# APD9328_FPGA_BANK.net
KiCad netlist of a schematic drawn in Altium Designer
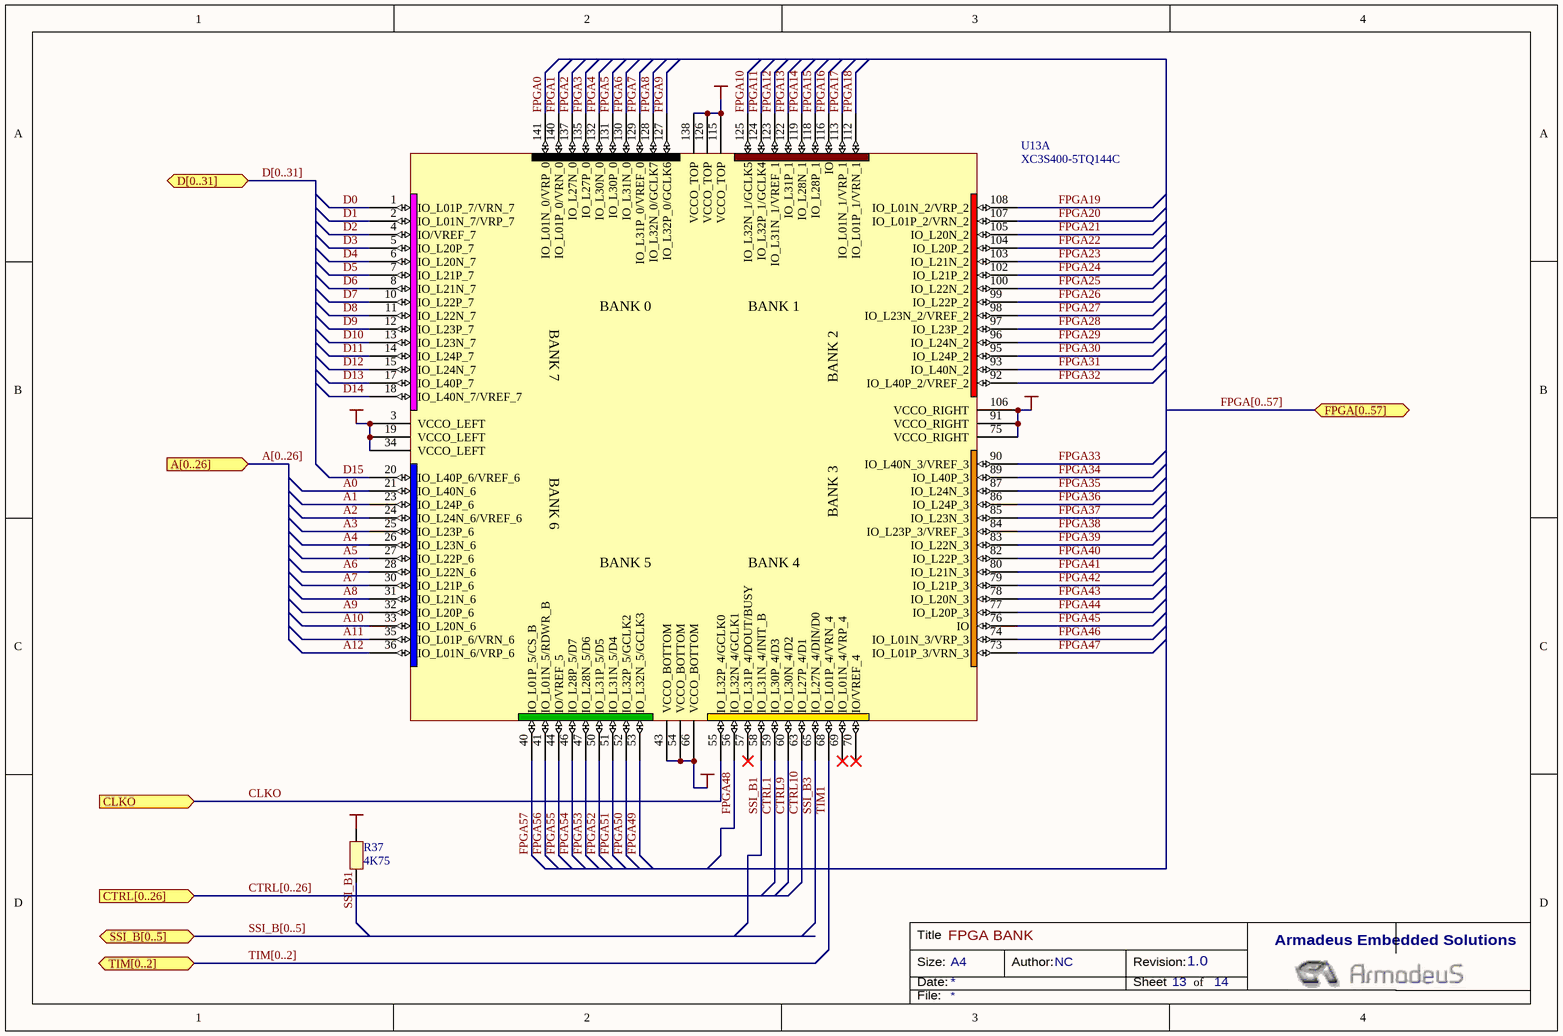
[diagram p0: APD9328_FPGA_BANK.SchDoc]

(export (version "E")
  (design (tool "Eeschema 10.0.6"))
  (components
    (comp (ref "R37") (value "4K75") (footprint "0402") (libsource (lib "*") (part "Res")))
    (comp (ref "U13")
      (value "XC3S400-5TQ144C")
      (footprint "TQ144")
      (description "Spartan-3 1.2V FPGA, 97 User I/Os, 144-pin TQFP, High Performance, Commercial Grade")
      (fields
        (field (name "MANUFACTURER") "Xilinx")
        (field (name "PART NUMBER") "XC3S400-4TQ144C")
        (field (name "PUBLISHER") "Altium Limited")
      )
      (libsource (lib "Xilinx Spartan-3") (part "XC3S400-5TQ144C"))
    )
  )
  (nets
    (net (code "61") (name "+3V3") (class "Default")
      (node (ref "R37") (pin "2") (pintype "passive"))
      (node (ref "U13") (pin "106") (pinfunction "VCCO_RIGHT_106") (pintype "power_in"))
      (node (ref "U13") (pin "115") (pinfunction "VCCO_TOP_115") (pintype "power_in"))
      (node (ref "U13") (pin "126") (pinfunction "VCCO_TOP_126") (pintype "power_in"))
      (node (ref "U13") (pin "138") (pinfunction "VCCO_TOP_138") (pintype "power_in"))
      (node (ref "U13") (pin "19") (pinfunction "VCCO_LEFT_19") (pintype "power_in"))
      (node (ref "U13") (pin "3") (pinfunction "VCCO_LEFT_3") (pintype "power_in"))
      (node (ref "U13") (pin "34") (pinfunction "VCCO_LEFT_34") (pintype "power_in"))
      (node (ref "U13") (pin "43") (pinfunction "VCCO_BOTTOM_43") (pintype "power_in"))
      (node (ref "U13") (pin "54") (pinfunction "VCCO_BOTTOM_54") (pintype "power_in"))
      (node (ref "U13") (pin "66") (pinfunction "VCCO_BOTTOM_66") (pintype "power_in"))
      (node (ref "U13") (pin "75") (pinfunction "VCCO_RIGHT_75") (pintype "power_in"))
      (node (ref "U13") (pin "91") (pinfunction "VCCO_RIGHT_91") (pintype "power_in"))
    )
    (net (code "62") (name "/A0") (class "Default")
      (node (ref "U13") (pin "21") (pinfunction "IO_L40N_6_21") (pintype "bidirectional"))
    )
    (net (code "63") (name "/A1") (class "Default")
      (node (ref "U13") (pin "23") (pinfunction "IO_L24P_6_23") (pintype "bidirectional"))
    )
    (net (code "64") (name "/A2") (class "Default")
      (node (ref "U13") (pin "24") (pinfunction "IO_L24N_6/VREF_6_24") (pintype "bidirectional"))
    )
    (net (code "65") (name "/A3") (class "Default")
      (node (ref "U13") (pin "25") (pinfunction "IO_L23P_6_25") (pintype "bidirectional"))
    )
    (net (code "66") (name "/A4") (class "Default")
      (node (ref "U13") (pin "26") (pinfunction "IO_L23N_6_26") (pintype "bidirectional"))
    )
    (net (code "67") (name "/A5") (class "Default")
      (node (ref "U13") (pin "27") (pinfunction "IO_L22P_6_27") (pintype "bidirectional"))
    )
    (net (code "68") (name "/A6") (class "Default")
      (node (ref "U13") (pin "28") (pinfunction "IO_L22N_6_28") (pintype "bidirectional"))
    )
    (net (code "69") (name "/A7") (class "Default")
      (node (ref "U13") (pin "30") (pinfunction "IO_L21P_6_30") (pintype "bidirectional"))
    )
    (net (code "70") (name "/A8") (class "Default")
      (node (ref "U13") (pin "31") (pinfunction "IO_L21N_6_31") (pintype "bidirectional"))
    )
    (net (code "71") (name "/A9") (class "Default")
      (node (ref "U13") (pin "32") (pinfunction "IO_L20P_6_32") (pintype "bidirectional"))
    )
    (net (code "72") (name "/A10") (class "Default")
      (node (ref "U13") (pin "33") (pinfunction "IO_L20N_6_33") (pintype "bidirectional"))
    )
    (net (code "73") (name "/A11") (class "Default")
      (node (ref "U13") (pin "35") (pinfunction "IO_L01P_6/VRN_6_35") (pintype "bidirectional"))
    )
    (net (code "74") (name "/A12") (class "Default")
      (node (ref "U13") (pin "36") (pinfunction "IO_L01N_6/VRP_6_36") (pintype "bidirectional"))
    )
    (net (code "76") (name "/CLKO") (class "Default")
      (node (ref "U13") (pin "55") (pinfunction "IO_L32P_4/GCLK0_55") (pintype "bidirectional"))
    )
    (net (code "77") (name "/CTRL1") (class "Default")
      (node (ref "U13") (pin "59") (pinfunction "IO_L30P_4/D3_59") (pintype "bidirectional"))
    )
    (net (code "78") (name "/CTRL9") (class "Default")
      (node (ref "U13") (pin "60") (pinfunction "IO_L30N_4/D2_60") (pintype "bidirectional"))
    )
    (net (code "79") (name "/CTRL10") (class "Default")
      (node (ref "U13") (pin "63") (pinfunction "IO_L27P_4/D1_63") (pintype "bidirectional"))
    )
    (net (code "81") (name "/D0") (class "Default")
      (node (ref "U13") (pin "1") (pinfunction "IO_L01P_7/VRN_7_1") (pintype "bidirectional"))
    )
    (net (code "82") (name "/D1") (class "Default")
      (node (ref "U13") (pin "2") (pinfunction "IO_L01N_7/VRP_7_2") (pintype "bidirectional"))
    )
    (net (code "83") (name "/D2") (class "Default")
      (node (ref "U13") (pin "4") (pinfunction "IO/VREF_7_4") (pintype "bidirectional"))
    )
    (net (code "84") (name "/D3") (class "Default")
      (node (ref "U13") (pin "5") (pinfunction "IO_L20P_7_5") (pintype "bidirectional"))
    )
    (net (code "85") (name "/D4") (class "Default")
      (node (ref "U13") (pin "6") (pinfunction "IO_L20N_7_6") (pintype "bidirectional"))
    )
    (net (code "86") (name "/D5") (class "Default")
      (node (ref "U13") (pin "7") (pinfunction "IO_L21P_7_7") (pintype "bidirectional"))
    )
    (net (code "87") (name "/D6") (class "Default")
      (node (ref "U13") (pin "8") (pinfunction "IO_L21N_7_8") (pintype "bidirectional"))
    )
    (net (code "88") (name "/D7") (class "Default")
      (node (ref "U13") (pin "10") (pinfunction "IO_L22P_7_10") (pintype "bidirectional"))
    )
    (net (code "89") (name "/D8") (class "Default")
      (node (ref "U13") (pin "11") (pinfunction "IO_L22N_7_11") (pintype "bidirectional"))
    )
    (net (code "90") (name "/D9") (class "Default")
      (node (ref "U13") (pin "12") (pinfunction "IO_L23P_7_12") (pintype "bidirectional"))
    )
    (net (code "91") (name "/D10") (class "Default")
      (node (ref "U13") (pin "13") (pinfunction "IO_L23N_7_13") (pintype "bidirectional"))
    )
    (net (code "92") (name "/D11") (class "Default")
      (node (ref "U13") (pin "14") (pinfunction "IO_L24P_7_14") (pintype "bidirectional"))
    )
    (net (code "93") (name "/D12") (class "Default")
      (node (ref "U13") (pin "15") (pinfunction "IO_L24N_7_15") (pintype "bidirectional"))
    )
    (net (code "94") (name "/D13") (class "Default")
      (node (ref "U13") (pin "17") (pinfunction "IO_L40P_7_17") (pintype "bidirectional"))
    )
    (net (code "95") (name "/D14") (class "Default")
      (node (ref "U13") (pin "18") (pinfunction "IO_L40N_7/VREF_7_18") (pintype "bidirectional"))
    )
    (net (code "96") (name "/D15") (class "Default")
      (node (ref "U13") (pin "20") (pinfunction "IO_L40P_6/VREF_6_20") (pintype "bidirectional"))
    )
    (net (code "98") (name "/FPGA0") (class "Default")
      (node (ref "U13") (pin "141") (pinfunction "IO_L01N_0/VRP_0_141") (pintype "bidirectional"))
    )
    (net (code "99") (name "/FPGA1") (class "Default")
      (node (ref "U13") (pin "140") (pinfunction "IO_L01P_0/VRN_0_140") (pintype "bidirectional"))
    )
    (net (code "100") (name "/FPGA2") (class "Default")
      (node (ref "U13") (pin "137") (pinfunction "IO_L27N_0_137") (pintype "bidirectional"))
    )
    (net (code "101") (name "/FPGA3") (class "Default")
      (node (ref "U13") (pin "135") (pinfunction "IO_L27P_0_135") (pintype "bidirectional"))
    )
    (net (code "102") (name "/FPGA4") (class "Default")
      (node (ref "U13") (pin "132") (pinfunction "IO_L30N_0_132") (pintype "bidirectional"))
    )
    (net (code "103") (name "/FPGA5") (class "Default")
      (node (ref "U13") (pin "131") (pinfunction "IO_L30P_0_131") (pintype "bidirectional"))
    )
    (net (code "104") (name "/FPGA6") (class "Default")
      (node (ref "U13") (pin "130") (pinfunction "IO_L31N_0_130") (pintype "bidirectional"))
    )
    (net (code "105") (name "/FPGA7") (class "Default")
      (node (ref "U13") (pin "129") (pinfunction "IO_L31P_0/VREF_0_129") (pintype "bidirectional"))
    )
    (net (code "106") (name "/FPGA8") (class "Default")
      (node (ref "U13") (pin "128") (pinfunction "IO_L32N_0/GCLK7_128") (pintype "bidirectional"))
    )
    (net (code "107") (name "/FPGA9") (class "Default")
      (node (ref "U13") (pin "127") (pinfunction "IO_L32P_0/GCLK6_127") (pintype "bidirectional"))
    )
    (net (code "108") (name "/FPGA10") (class "Default")
      (node (ref "U13") (pin "125") (pinfunction "IO_L32N_1/GCLK5_125") (pintype "bidirectional"))
    )
    (net (code "109") (name "/FPGA11") (class "Default")
      (node (ref "U13") (pin "124") (pinfunction "IO_L32P_1/GCLK4_124") (pintype "bidirectional"))
    )
    (net (code "110") (name "/FPGA12") (class "Default")
      (node (ref "U13") (pin "123") (pinfunction "IO_L31N_1/VREF_1_123") (pintype "bidirectional"))
    )
    (net (code "111") (name "/FPGA13") (class "Default")
      (node (ref "U13") (pin "122") (pinfunction "IO_L31P_1_122") (pintype "bidirectional"))
    )
    (net (code "112") (name "/FPGA14") (class "Default")
      (node (ref "U13") (pin "119") (pinfunction "IO_L28N_1_119") (pintype "bidirectional"))
    )
    (net (code "113") (name "/FPGA15") (class "Default")
      (node (ref "U13") (pin "118") (pinfunction "IO_L28P_1_118") (pintype "bidirectional"))
    )
    (net (code "114") (name "/FPGA16") (class "Default")
      (node (ref "U13") (pin "116") (pinfunction "IO_116") (pintype "bidirectional"))
    )
    (net (code "115") (name "/FPGA17") (class "Default")
      (node (ref "U13") (pin "113") (pinfunction "IO_L01N_1/VRP_1_113") (pintype "bidirectional"))
    )
    (net (code "116") (name "/FPGA18") (class "Default")
      (node (ref "U13") (pin "112") (pinfunction "IO_L01P_1/VRN_1_112") (pintype "bidirectional"))
    )
    (net (code "117") (name "/FPGA19") (class "Default")
      (node (ref "U13") (pin "108") (pinfunction "IO_L01N_2/VRP_2_108") (pintype "bidirectional"))
    )
    (net (code "118") (name "/FPGA20") (class "Default")
      (node (ref "U13") (pin "107") (pinfunction "IO_L01P_2/VRN_2_107") (pintype "bidirectional"))
    )
    (net (code "119") (name "/FPGA21") (class "Default")
      (node (ref "U13") (pin "105") (pinfunction "IO_L20N_2_105") (pintype "bidirectional"))
    )
    (net (code "120") (name "/FPGA22") (class "Default")
      (node (ref "U13") (pin "104") (pinfunction "IO_L20P_2_104") (pintype "bidirectional"))
    )
    (net (code "121") (name "/FPGA23") (class "Default")
      (node (ref "U13") (pin "103") (pinfunction "IO_L21N_2_103") (pintype "bidirectional"))
    )
    (net (code "122") (name "/FPGA24") (class "Default")
      (node (ref "U13") (pin "102") (pinfunction "IO_L21P_2_102") (pintype "bidirectional"))
    )
    (net (code "123") (name "/FPGA25") (class "Default")
      (node (ref "U13") (pin "100") (pinfunction "IO_L22N_2_100") (pintype "bidirectional"))
    )
    (net (code "124") (name "/FPGA26") (class "Default")
      (node (ref "U13") (pin "99") (pinfunction "IO_L22P_2_99") (pintype "bidirectional"))
    )
    (net (code "125") (name "/FPGA27") (class "Default")
      (node (ref "U13") (pin "98") (pinfunction "IO_L23N_2/VREF_2_98") (pintype "bidirectional"))
    )
    (net (code "126") (name "/FPGA28") (class "Default")
      (node (ref "U13") (pin "97") (pinfunction "IO_L23P_2_97") (pintype "bidirectional"))
    )
    (net (code "127") (name "/FPGA29") (class "Default")
      (node (ref "U13") (pin "96") (pinfunction "IO_L24N_2_96") (pintype "bidirectional"))
    )
    (net (code "128") (name "/FPGA30") (class "Default")
      (node (ref "U13") (pin "95") (pinfunction "IO_L24P_2_95") (pintype "bidirectional"))
    )
    (net (code "129") (name "/FPGA31") (class "Default")
      (node (ref "U13") (pin "93") (pinfunction "IO_L40N_2_93") (pintype "bidirectional"))
    )
    (net (code "130") (name "/FPGA32") (class "Default")
      (node (ref "U13") (pin "92") (pinfunction "IO_L40P_2/VREF_2_92") (pintype "bidirectional"))
    )
    (net (code "131") (name "/FPGA33") (class "Default")
      (node (ref "U13") (pin "90") (pinfunction "IO_L40N_3/VREF_3_90") (pintype "bidirectional"))
    )
    (net (code "132") (name "/FPGA34") (class "Default")
      (node (ref "U13") (pin "89") (pinfunction "IO_L40P_3_89") (pintype "bidirectional"))
    )
    (net (code "133") (name "/FPGA35") (class "Default")
      (node (ref "U13") (pin "87") (pinfunction "IO_L24N_3_87") (pintype "bidirectional"))
    )
    (net (code "134") (name "/FPGA36") (class "Default")
      (node (ref "U13") (pin "86") (pinfunction "IO_L24P_3_86") (pintype "bidirectional"))
    )
    (net (code "135") (name "/FPGA37") (class "Default")
      (node (ref "U13") (pin "85") (pinfunction "IO_L23N_3_85") (pintype "bidirectional"))
    )
    (net (code "136") (name "/FPGA38") (class "Default")
      (node (ref "U13") (pin "84") (pinfunction "IO_L23P_3/VREF_3_84") (pintype "bidirectional"))
    )
    (net (code "137") (name "/FPGA39") (class "Default")
      (node (ref "U13") (pin "83") (pinfunction "IO_L22N_3_83") (pintype "bidirectional"))
    )
    (net (code "138") (name "/FPGA40") (class "Default")
      (node (ref "U13") (pin "82") (pinfunction "IO_L22P_3_82") (pintype "bidirectional"))
    )
    (net (code "139") (name "/FPGA41") (class "Default")
      (node (ref "U13") (pin "80") (pinfunction "IO_L21N_3_80") (pintype "bidirectional"))
    )
    (net (code "140") (name "/FPGA42") (class "Default")
      (node (ref "U13") (pin "79") (pinfunction "IO_L21P_3_79") (pintype "bidirectional"))
    )
    (net (code "141") (name "/FPGA43") (class "Default")
      (node (ref "U13") (pin "78") (pinfunction "IO_L20N_3_78") (pintype "bidirectional"))
    )
    (net (code "142") (name "/FPGA44") (class "Default")
      (node (ref "U13") (pin "77") (pinfunction "IO_L20P_3_77") (pintype "bidirectional"))
    )
    (net (code "143") (name "/FPGA45") (class "Default")
      (node (ref "U13") (pin "76") (pinfunction "IO_76") (pintype "bidirectional"))
    )
    (net (code "144") (name "/FPGA46") (class "Default")
      (node (ref "U13") (pin "74") (pinfunction "IO_L01N_3/VRP_3_74") (pintype "bidirectional"))
    )
    (net (code "145") (name "/FPGA47") (class "Default")
      (node (ref "U13") (pin "73") (pinfunction "IO_L01P_3/VRN_3_73") (pintype "bidirectional"))
    )
    (net (code "146") (name "/FPGA48") (class "Default")
      (node (ref "U13") (pin "56") (pinfunction "IO_L32N_4/GCLK1_56") (pintype "bidirectional"))
    )
    (net (code "147") (name "/FPGA49") (class "Default")
      (node (ref "U13") (pin "53") (pinfunction "IO_L32N_5/GCLK3_53") (pintype "bidirectional"))
    )
    (net (code "148") (name "/FPGA50") (class "Default")
      (node (ref "U13") (pin "52") (pinfunction "IO_L32P_5/GCLK2_52") (pintype "bidirectional"))
    )
    (net (code "149") (name "/FPGA51") (class "Default")
      (node (ref "U13") (pin "51") (pinfunction "IO_L31N_5/D4_51") (pintype "bidirectional"))
    )
    (net (code "150") (name "/FPGA52") (class "Default")
      (node (ref "U13") (pin "50") (pinfunction "IO_L31P_5/D5_50") (pintype "bidirectional"))
    )
    (net (code "151") (name "/FPGA53") (class "Default")
      (node (ref "U13") (pin "47") (pinfunction "IO_L28N_5/D6_47") (pintype "bidirectional"))
    )
    (net (code "152") (name "/FPGA54") (class "Default")
      (node (ref "U13") (pin "46") (pinfunction "IO_L28P_5/D7_46") (pintype "bidirectional"))
    )
    (net (code "153") (name "/FPGA55") (class "Default")
      (node (ref "U13") (pin "44") (pinfunction "IO/VREF_5_44") (pintype "bidirectional"))
    )
    (net (code "154") (name "/FPGA56") (class "Default")
      (node (ref "U13") (pin "41") (pinfunction "IO_L01N_5/RDWR_B_41") (pintype "bidirectional"))
    )
    (net (code "155") (name "/FPGA57") (class "Default")
      (node (ref "U13") (pin "40") (pinfunction "IO_L01P_5/CS_B_40") (pintype "bidirectional"))
    )
    (net (code "157") (name "/SSI_B1") (class "Default")
      (node (ref "R37") (pin "1") (pintype "passive"))
      (node (ref "U13") (pin "58") (pinfunction "IO_L31N_4/INIT_B_58") (pintype "bidirectional"))
    )
    (net (code "158") (name "/SSI_B3") (class "Default")
      (node (ref "U13") (pin "65") (pinfunction "IO_L27N_4/DIN/D0_65") (pintype "bidirectional"))
    )
    (net (code "160") (name "/TIM1") (class "Default")
      (node (ref "U13") (pin "68") (pinfunction "IO_L01P_4/VRN_4_68") (pintype "bidirectional"))
    )
    (net (code "162") (name "unconnected-(U13A-IO_L01N_4{slash}VRP_4-Pad69)") (class "Default")
      (node (ref "U13") (pin "69") (pinfunction "IO_L01N_4/VRP_4_69") (pintype "bidirectional+no_connect"))
    )
    (net (code "163") (name "unconnected-(U13A-IO_L31P_4{slash}DOUT{slash}BUSY-Pad57)") (class "Default")
      (node (ref "U13") (pin "57") (pinfunction "IO_L31P_4/DOUT/BUSY_57") (pintype "bidirectional+no_connect"))
    )
    (net (code "164") (name "unconnected-(U13A-IO{slash}VREF_4-Pad70)") (class "Default")
      (node (ref "U13") (pin "70") (pinfunction "IO/VREF_4_70") (pintype "bidirectional+no_connect"))
    )
  )
)
